# InkTime_Schematic.net
KiCad netlist of a schematic drawn in EAGLE
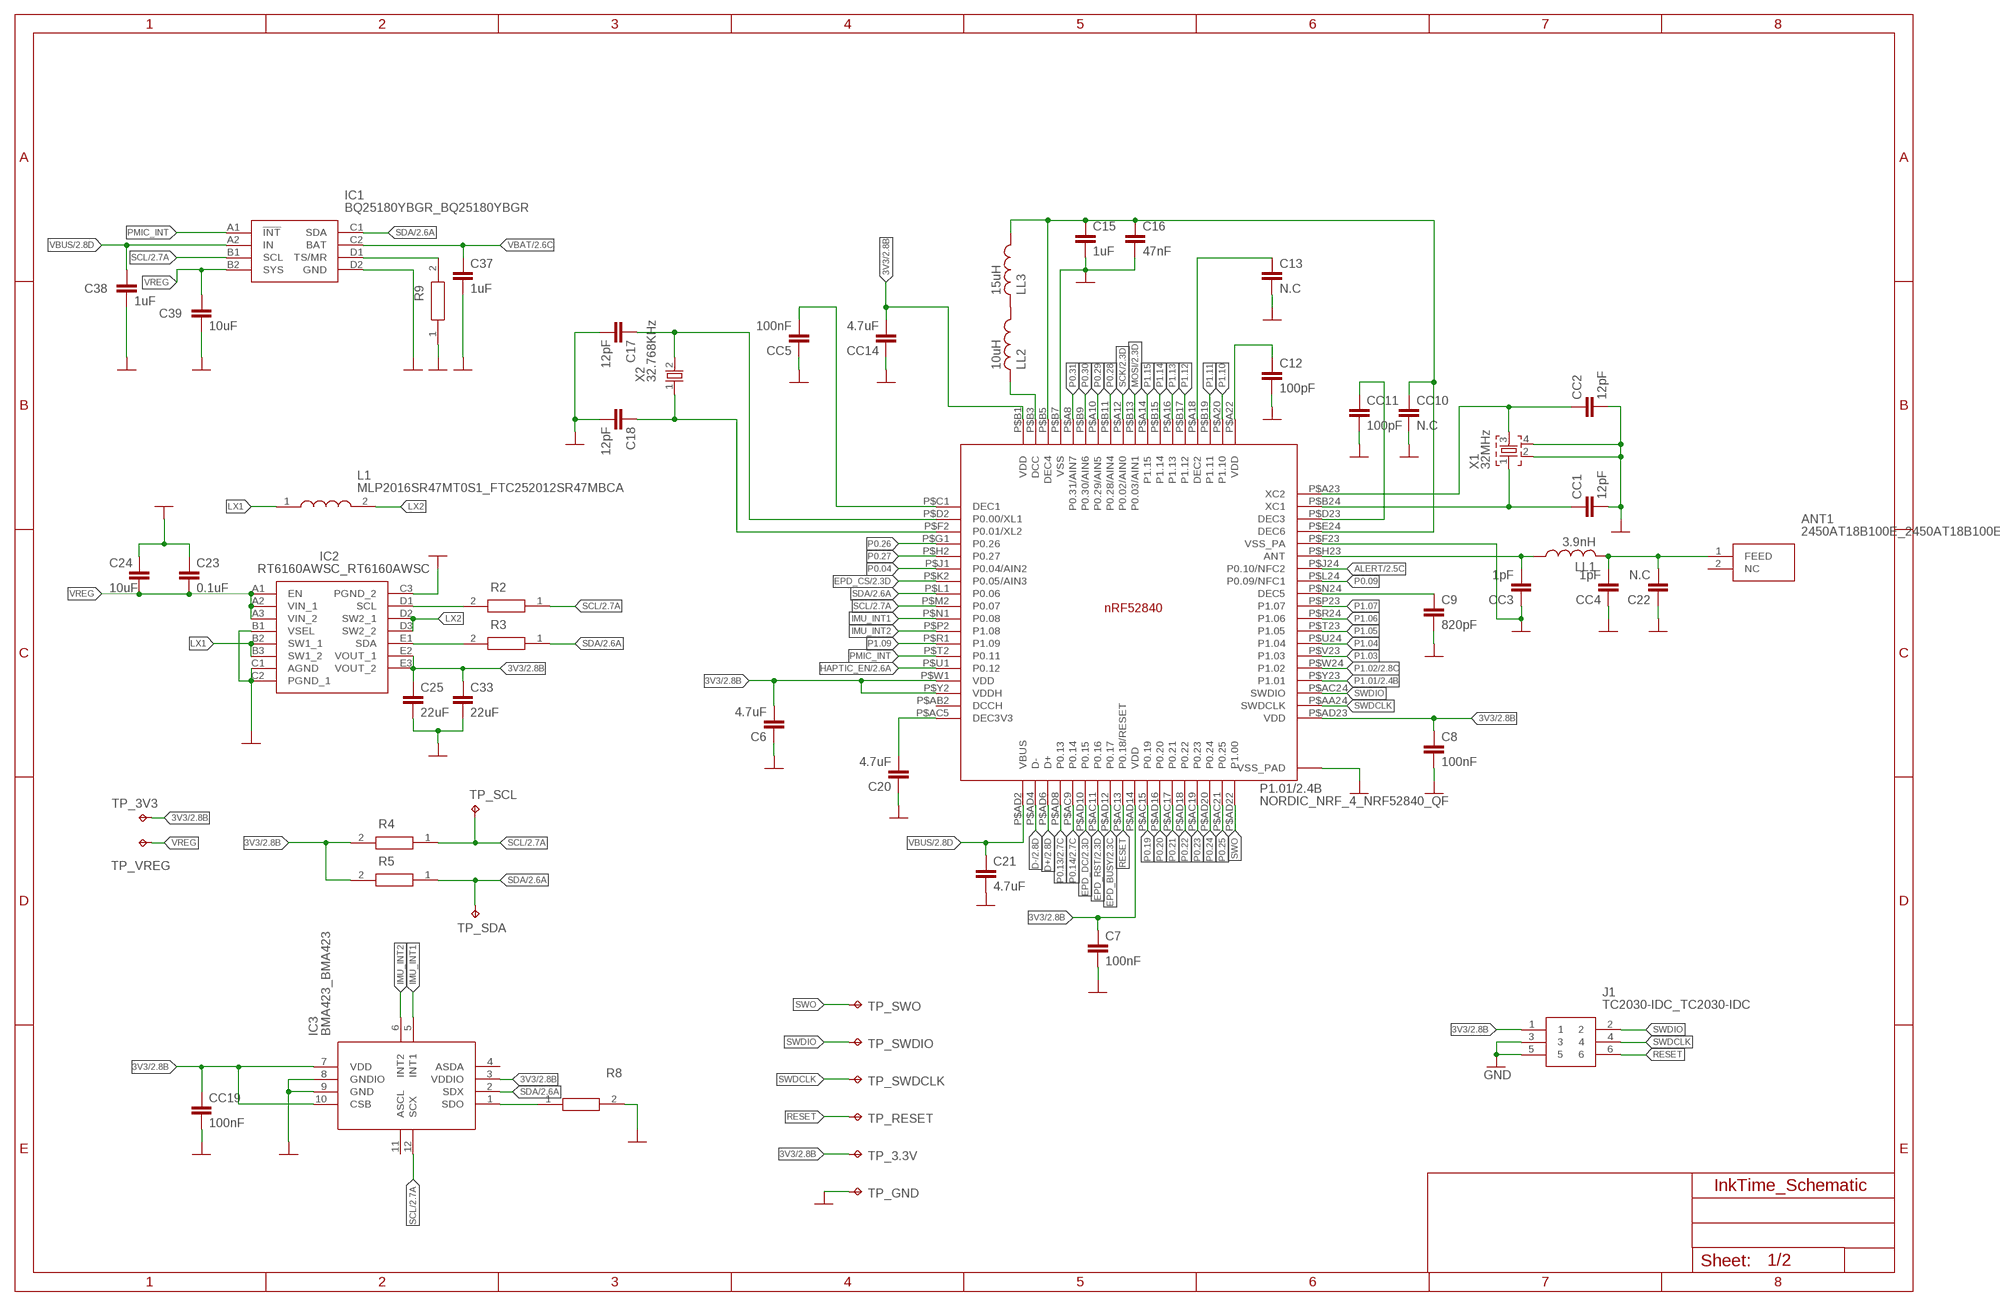
[diagram p0: schematic, sheet 1]
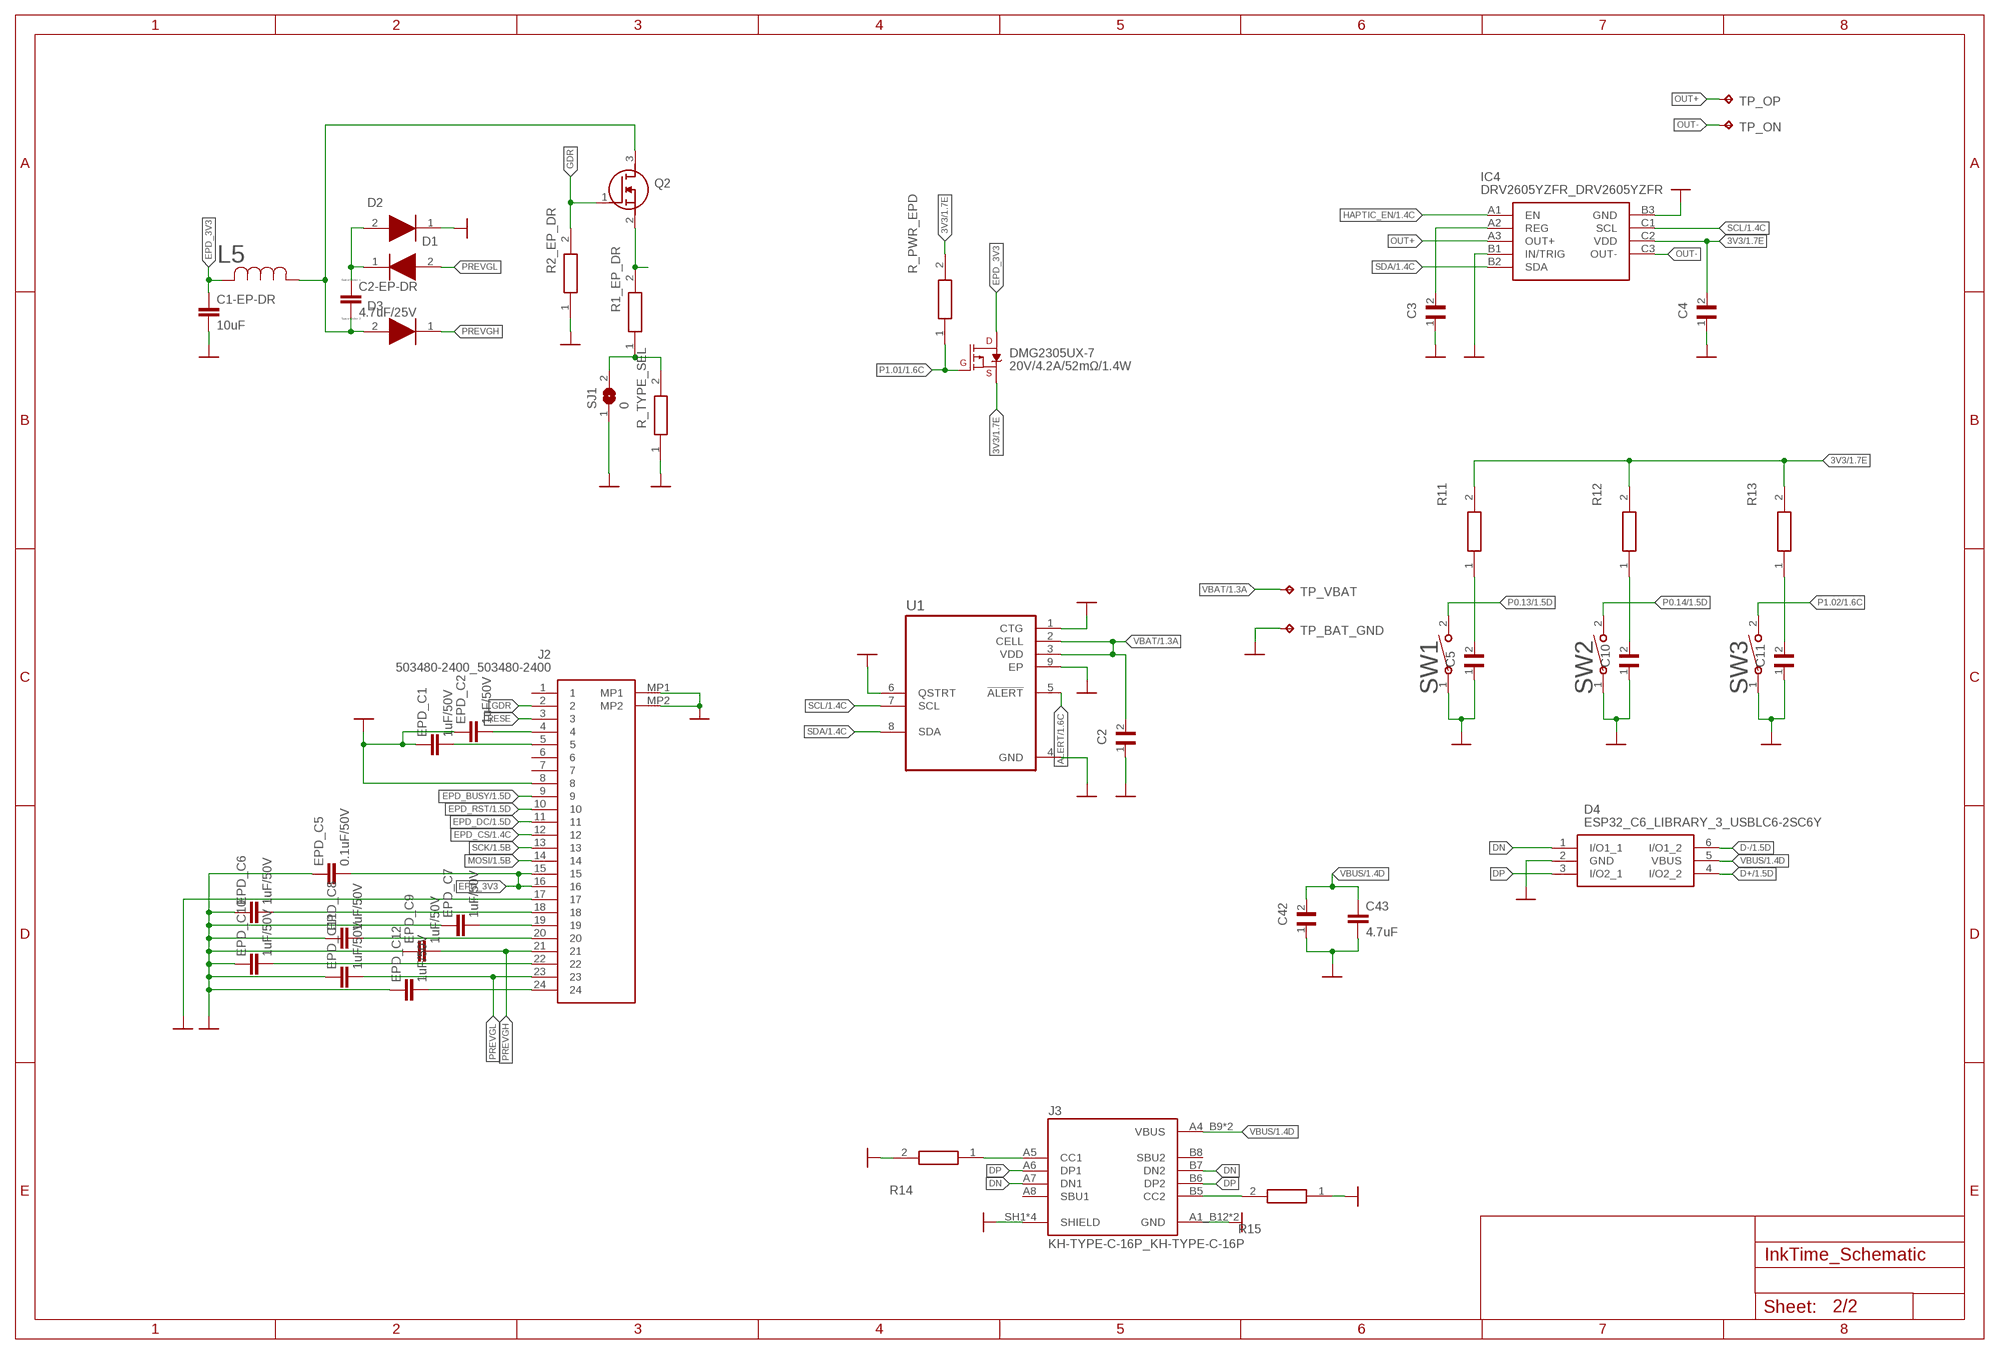
[diagram p1: schematic, sheet 2]

(export (version "E")
  (design (tool "Eeschema 10.0.6"))
  (components
    (comp (ref "C1-EP-DR")
      (value "10uF")
      (footprint "eagle-import:NORDIC_NRF_3_RESC0402_M")
      (libsource (lib "eagle-import") (part "NORDIC_NRF_3_CAPACITOR_0402_M"))
    )
    (comp (ref "C2")
      (value "GRM011R60J152KE01L_1_GRM011R60J152KE01L")
      (footprint "eagle-import:GRM011R60J152KE01L_1_0201")
      (libsource (lib "eagle-import") (part "GRM011R60J152KE01L_1_GRM011R60J152KE01L"))
    )
    (comp (ref "C2-EP-DR")
      (value "4.7uF/25V")
      (footprint "eagle-import:ESP32_C6_LIBRARY_1_ESP32_WROVER_EAGLE-LTSPICE_C0402")
      (libsource (lib "eagle-import") (part "ESP32_C6_LIBRARY_1_ESP32_WROVER_EAGLE-LTSPICE_CC0402"))
    )
    (comp (ref "C3")
      (value "1uF")
      (footprint "eagle-import:GRM011R60J152KE01L_1_0201")
      (libsource (lib "eagle-import") (part "GRM011R60J152KE01L_1_GRM011R60J152KE01L"))
    )
    (comp (ref "C4")
      (value "0.1uF")
      (footprint "eagle-import:GRM011R60J152KE01L_1_0201")
      (libsource (lib "eagle-import") (part "GRM011R60J152KE01L_1_GRM011R60J152KE01L"))
    )
    (comp (ref "C5")
      (value "GRM011R60J152KE01L_1_GRM011R60J152KE01L")
      (footprint "eagle-import:GRM011R60J152KE01L_1_0201")
      (libsource (lib "eagle-import") (part "GRM011R60J152KE01L_1_GRM011R60J152KE01L"))
    )
    (comp (ref "C10")
      (value "GRM011R60J152KE01L_1_GRM011R60J152KE01L")
      (footprint "eagle-import:GRM011R60J152KE01L_1_0201")
      (libsource (lib "eagle-import") (part "GRM011R60J152KE01L_1_GRM011R60J152KE01L"))
    )
    (comp (ref "C11")
      (value "GRM011R60J152KE01L_1_GRM011R60J152KE01L")
      (footprint "eagle-import:GRM011R60J152KE01L_1_0201")
      (libsource (lib "eagle-import") (part "GRM011R60J152KE01L_1_GRM011R60J152KE01L"))
    )
    (comp (ref "C42")
      (value "GRM011R60J152KE01L_1_GRM011R60J152KE01L")
      (footprint "eagle-import:GRM011R60J152KE01L_1_0201")
      (libsource (lib "eagle-import") (part "GRM011R60J152KE01L_1_GRM011R60J152KE01L"))
    )
    (comp (ref "C43")
      (value "4.7uF")
      (footprint "eagle-import:NORDIC_NRF_3_RESC0402_M")
      (libsource (lib "eagle-import") (part "NORDIC_NRF_3_CAPACITOR_0402_M"))
    )
    (comp (ref "D1")
      (value "ESP32_C6_LIBRARY_5_MBR0530")
      (footprint "eagle-import:ESP32_C6_LIBRARY_5_SOD3716X135N")
      (fields (field (name "MF") "ON Semiconductor") (field (name "MP") "MBR0530"))
      (libsource (lib "eagle-import") (part "ESP32_C6_LIBRARY_5_MBR0530"))
    )
    (comp (ref "D2")
      (value "ESP32_C6_LIBRARY_5_MBR0530")
      (footprint "eagle-import:ESP32_C6_LIBRARY_5_SOD3716X135N")
      (fields (field (name "MF") "ON Semiconductor") (field (name "MP") "MBR0530"))
      (libsource (lib "eagle-import") (part "ESP32_C6_LIBRARY_5_MBR0530"))
    )
    (comp (ref "D3")
      (value "ESP32_C6_LIBRARY_5_MBR0530")
      (footprint "eagle-import:ESP32_C6_LIBRARY_5_SOD3716X135N")
      (fields (field (name "MF") "ON Semiconductor") (field (name "MP") "MBR0530"))
      (libsource (lib "eagle-import") (part "ESP32_C6_LIBRARY_5_MBR0530"))
    )
    (comp (ref "D4")
      (value "ESP32_C6_LIBRARY_3_USBLC6-2SC6Y")
      (footprint "eagle-import:ESP32_C6_LIBRARY_3_SOT95P280X145-6N")
      (fields (field (name "MF") "STMicroelectronics") (field (name "MP") "USBLC6-2SC6Y"))
      (libsource (lib "eagle-import") (part "ESP32_C6_LIBRARY_3_USBLC6-2SC6Y"))
    )
    (comp (ref "DMG2305UX-7")
      (value "20V/4.2A/52mΩ/1.4W")
      (footprint "eagle-import:ESP32_C6_LIBRARY_4_ESP32_C6_LIBRARY_4_ESP32_C6_LIBRARY_4_ESP32_C6_LIBRARY_4_ESP32_WROVER_SPARKFUN-DISCRETESEMI_SOT23-3")
      (libsource (lib "eagle-import") (part "ESP32_C6_LIBRARY_4_ESP32_WROVER_SPARKFUN-DISCRETESEMI_MOSFET_PCH-DMG2305UX-7"))
    )
    (comp (ref "EPD_C1")
      (value "1uF/50V")
      (footprint "eagle-import:NORDIC_NRF_3_RESC0402_M")
      (libsource (lib "eagle-import") (part "NORDIC_NRF_3_CAPACITOR_0402_M"))
    )
    (comp (ref "EPD_C2")
      (value "1uF/50V")
      (footprint "eagle-import:NORDIC_NRF_3_RESC0402_M")
      (libsource (lib "eagle-import") (part "NORDIC_NRF_3_CAPACITOR_0402_M"))
    )
    (comp (ref "EPD_C5")
      (value "0.1uF/50V")
      (footprint "eagle-import:NORDIC_NRF_3_RESC0402_M")
      (libsource (lib "eagle-import") (part "NORDIC_NRF_3_CAPACITOR_0402_M"))
    )
    (comp (ref "EPD_C6")
      (value "1uF/50V")
      (footprint "eagle-import:NORDIC_NRF_3_RESC0402_M")
      (libsource (lib "eagle-import") (part "NORDIC_NRF_3_CAPACITOR_0402_M"))
    )
    (comp (ref "EPD_C7")
      (value "1uF/50V")
      (footprint "eagle-import:NORDIC_NRF_3_RESC0402_M")
      (libsource (lib "eagle-import") (part "NORDIC_NRF_3_CAPACITOR_0402_M"))
    )
    (comp (ref "EPD_C8")
      (value "1uF/50V")
      (footprint "eagle-import:NORDIC_NRF_3_RESC0402_M")
      (libsource (lib "eagle-import") (part "NORDIC_NRF_3_CAPACITOR_0402_M"))
    )
    (comp (ref "EPD_C9")
      (value "1uF/50V")
      (footprint "eagle-import:NORDIC_NRF_3_RESC0402_M")
      (libsource (lib "eagle-import") (part "NORDIC_NRF_3_CAPACITOR_0402_M"))
    )
    (comp (ref "EPD_C10")
      (value "1uF/50V")
      (footprint "eagle-import:NORDIC_NRF_3_RESC0402_M")
      (libsource (lib "eagle-import") (part "NORDIC_NRF_3_CAPACITOR_0402_M"))
    )
    (comp (ref "EPD_C11")
      (value "1uF/50V")
      (footprint "eagle-import:NORDIC_NRF_3_RESC0402_M")
      (libsource (lib "eagle-import") (part "NORDIC_NRF_3_CAPACITOR_0402_M"))
    )
    (comp (ref "EPD_C12")
      (value "1uF/50V")
      (footprint "eagle-import:NORDIC_NRF_3_RESC0402_M")
      (libsource (lib "eagle-import") (part "NORDIC_NRF_3_CAPACITOR_0402_M"))
    )
    (comp (ref "IC4")
      (value "DRV2605YZFR_DRV2605YZFR")
      (footprint "eagle-import:DRV2605YZFR_BGA9C50P3X3_144X144X62")
      (fields (field (name "ARROW_PART_NUMBER") "DRV2605YZFR"))
      (libsource (lib "eagle-import") (part "DRV2605YZFR_DRV2605YZFR"))
    )
    (comp (ref "J2")
      (value "503480-2400_503480-2400")
      (footprint "eagle-import:503480-2400_5034802400")
      (fields
        (field (name "MANUFACTURER_PART_NUMBER") "503480-2400")
        (field (name "MOUSER_PART_NUMBER") "538-503480-2400")
      )
      (libsource (lib "eagle-import") (part "503480-2400_503480-2400"))
    )
    (comp (ref "J3")
      (value "KH-TYPE-C-16P_KH-TYPE-C-16P")
      (footprint "eagle-import:KH-TYPE-C-16P_KINGHELM_KH-TYPE-C-16P")
      (fields (field (name "MF") "kinghelm") (field (name "MP") "KH-TYPE-C-16P"))
      (libsource (lib "eagle-import") (part "KH-TYPE-C-16P_KH-TYPE-C-16P"))
    )
    (comp (ref "L5")
      (value "ESP32_C6_LIBRARY_2_744043680IND_4828-WE-TPC_WRE")
      (footprint "eagle-import:ESP32_C6_LIBRARY_2_IND_4828-WE-TPC_WRE")
      (fields
        (field (name "MANUFACTURER_PART_NUMBER") "744043680")
        (field (name "COPYRIGHT") "Copyright (C) 2024 Ultra Librarian. All rights reserved.")
      )
      (libsource (lib "eagle-import") (part "ESP32_C6_LIBRARY_2_744043680IND_4828-WE-TPC_WRE"))
    )
    (comp (ref "Q2")
      (value "ESP32_C6_LIBRARY_6_SI1308EDL-T1-GE3")
      (footprint "eagle-import:ESP32_C6_LIBRARY_6_SOT65P210X110-3N")
      (fields (field (name "MF") "Vishay Siliconix") (field (name "MP") "SI1308EDL-T1-GE3"))
      (libsource (lib "eagle-import") (part "ESP32_C6_LIBRARY_6_SI1308EDL-T1-GE3"))
    )
    (comp (ref "R1_EP_DR")
      (value "CPF0201D7K68C1_CPF0201D7K68C1")
      (footprint "eagle-import:CPF0201D7K68C1_0201")
      (libsource (lib "eagle-import") (part "CPF0201D7K68C1_CPF0201D7K68C1"))
    )
    (comp (ref "R2_EP_DR")
      (value "CPF0201D7K68C1_CPF0201D7K68C1")
      (footprint "eagle-import:CPF0201D7K68C1_0201")
      (libsource (lib "eagle-import") (part "CPF0201D7K68C1_CPF0201D7K68C1"))
    )
    (comp (ref "R11")
      (value "CPF0201D7K68C1_CPF0201D7K68C1")
      (footprint "eagle-import:CPF0201D7K68C1_0201")
      (libsource (lib "eagle-import") (part "CPF0201D7K68C1_CPF0201D7K68C1"))
    )
    (comp (ref "R12")
      (value "CPF0201D7K68C1_CPF0201D7K68C1")
      (footprint "eagle-import:CPF0201D7K68C1_0201")
      (libsource (lib "eagle-import") (part "CPF0201D7K68C1_CPF0201D7K68C1"))
    )
    (comp (ref "R13")
      (value "CPF0201D7K68C1_CPF0201D7K68C1")
      (footprint "eagle-import:CPF0201D7K68C1_0201")
      (libsource (lib "eagle-import") (part "CPF0201D7K68C1_CPF0201D7K68C1"))
    )
    (comp (ref "R14")
      (value "CPF0201D7K68C1_CPF0201D7K68C1")
      (footprint "eagle-import:CPF0201D7K68C1_0201")
      (libsource (lib "eagle-import") (part "CPF0201D7K68C1_CPF0201D7K68C1"))
    )
    (comp (ref "R15")
      (value "CPF0201D7K68C1_CPF0201D7K68C1")
      (footprint "eagle-import:CPF0201D7K68C1_0201")
      (libsource (lib "eagle-import") (part "CPF0201D7K68C1_CPF0201D7K68C1"))
    )
    (comp (ref "R_PWR_EPD")
      (value "CPF0201D7K68C1_CPF0201D7K68C1")
      (footprint "eagle-import:CPF0201D7K68C1_0201")
      (libsource (lib "eagle-import") (part "CPF0201D7K68C1_CPF0201D7K68C1"))
    )
    (comp (ref "R_TYPE_SEL")
      (value "CPF0201D7K68C1_CPF0201D7K68C1")
      (footprint "eagle-import:CPF0201D7K68C1_0201")
      (libsource (lib "eagle-import") (part "CPF0201D7K68C1_CPF0201D7K68C1"))
    )
    (comp (ref "SJ1")
      (value "0")
      (footprint "eagle-import:ESP32_C6_LIBRARY_7_JUMPER_SJ")
      (libsource (lib "eagle-import") (part "ESP32_C6_LIBRARY_7_JUMPER_SJ"))
    )
    (comp (ref "SW1")
      (value "2025-10-22_07-23-44_LIBRARY_EVP-AKE31ASW_EVP-AKE31A_PAN")
      (footprint "eagle-import:2025-10-22_07-23-44_LIBRARY_SW_EVP-AKE31A_PAN")
      (fields
        (field (name "MANUFACTURER_PART_NUMBER") "EVP-AKE31A")
        (field (name "COPYRIGHT") "Copyright (C) 2025 Ultra Librarian. All rights reserved.")
      )
      (libsource (lib "eagle-import") (part "2025-10-22_07-23-44_LIBRARY_EVP-AKE31ASW_EVP-AKE31A_PAN"))
    )
    (comp (ref "SW2")
      (value "2025-10-22_07-23-44_LIBRARY_EVP-AKE31ASW_EVP-AKE31A_PAN")
      (footprint "eagle-import:2025-10-22_07-23-44_LIBRARY_SW_EVP-AKE31A_PAN")
      (fields
        (field (name "MANUFACTURER_PART_NUMBER") "EVP-AKE31A")
        (field (name "COPYRIGHT") "Copyright (C) 2025 Ultra Librarian. All rights reserved.")
      )
      (libsource (lib "eagle-import") (part "2025-10-22_07-23-44_LIBRARY_EVP-AKE31ASW_EVP-AKE31A_PAN"))
    )
    (comp (ref "SW3")
      (value "2025-10-22_07-23-44_LIBRARY_EVP-AKE31ASW_EVP-AKE31A_PAN")
      (footprint "eagle-import:2025-10-22_07-23-44_LIBRARY_SW_EVP-AKE31A_PAN")
      (fields
        (field (name "MANUFACTURER_PART_NUMBER") "EVP-AKE31A")
        (field (name "COPYRIGHT") "Copyright (C) 2025 Ultra Librarian. All rights reserved.")
      )
      (libsource (lib "eagle-import") (part "2025-10-22_07-23-44_LIBRARY_EVP-AKE31ASW_EVP-AKE31A_PAN"))
    )
    (comp (ref "TP_BAT_GND")
      (value "HECTOR_WATCH_1_TPTP20R")
      (footprint "eagle-import:HECTOR_WATCH_1_TP20R")
      (libsource (lib "eagle-import") (part "HECTOR_WATCH_1_TPTP20R"))
    )
    (comp (ref "TP_ON")
      (value "HECTOR_WATCH_1_TPTP20R")
      (footprint "eagle-import:HECTOR_WATCH_1_TP20R")
      (libsource (lib "eagle-import") (part "HECTOR_WATCH_1_TPTP20R"))
    )
    (comp (ref "TP_OP")
      (value "HECTOR_WATCH_1_TPTP20R")
      (footprint "eagle-import:HECTOR_WATCH_1_TP20R")
      (libsource (lib "eagle-import") (part "HECTOR_WATCH_1_TPTP20R"))
    )
    (comp (ref "TP_VBAT")
      (value "HECTOR_WATCH_1_TPTP20R")
      (footprint "eagle-import:HECTOR_WATCH_1_TP20R")
      (libsource (lib "eagle-import") (part "HECTOR_WATCH_1_TPTP20R"))
    )
    (comp (ref "U1")
      (value "ESP32_C6_LIBRARY_MAX17048G+T10")
      (footprint "eagle-import:ESP32_C6_LIBRARY_SON50P200X200X80-9N")
      (fields (field (name "MF") "Analog Devices") (field (name "MP") "MAX17048G+T10"))
      (libsource (lib "eagle-import") (part "ESP32_C6_LIBRARY_MAX17048G+T10"))
    )
    (comp (ref "ANT1")
      (value "2450AT18B100E_2450AT18B100E")
      (footprint "eagle-import:2450AT18B100E_ANTC3216X140N")
      (fields
        (field (name "ARROW_PART_NUMBER") "2450AT18B100E")
        (field (name "MOUSER_PART_NUMBER") "609-2450AT18B100E")
      )
      (libsource (lib "eagle-import") (part "2450AT18B100E_2450AT18B100E"))
    )
    (comp (ref "C6")
      (value "4.7uF")
      (footprint "eagle-import:NORDIC_NRF_3_RESC0402_M")
      (libsource (lib "eagle-import") (part "NORDIC_NRF_3_CAPACITOR_0402_M"))
    )
    (comp (ref "C7")
      (value "100nF")
      (footprint "eagle-import:NORDIC_NRF_3_RESC0402_M")
      (libsource (lib "eagle-import") (part "NORDIC_NRF_3_CAPACITOR_0402_M"))
    )
    (comp (ref "C8")
      (value "100nF")
      (footprint "eagle-import:NORDIC_NRF_3_RESC0402_M")
      (libsource (lib "eagle-import") (part "NORDIC_NRF_3_CAPACITOR_0402_M"))
    )
    (comp (ref "C9")
      (value "820pF")
      (footprint "eagle-import:NORDIC_NRF_3_RESC0402_M")
      (libsource (lib "eagle-import") (part "NORDIC_NRF_3_CAPACITOR_0402_M"))
    )
    (comp (ref "C12")
      (value "100pF")
      (footprint "eagle-import:NORDIC_NRF_3_RESC0402_M")
      (libsource (lib "eagle-import") (part "NORDIC_NRF_3_CAPACITOR_0402_M"))
    )
    (comp (ref "C13")
      (value "N.C")
      (footprint "eagle-import:NORDIC_NRF_3_RESC0402_M")
      (libsource (lib "eagle-import") (part "NORDIC_NRF_3_CAPACITOR_0402_M"))
    )
    (comp (ref "C15")
      (value "1uF")
      (footprint "eagle-import:NORDIC_NRF_3_RESC0402_M")
      (libsource (lib "eagle-import") (part "NORDIC_NRF_3_CAPACITOR_0402_M"))
    )
    (comp (ref "C16")
      (value "47nF")
      (footprint "eagle-import:NORDIC_NRF_3_RESC0402_M")
      (libsource (lib "eagle-import") (part "NORDIC_NRF_3_CAPACITOR_0402_M"))
    )
    (comp (ref "C17")
      (value "12pF")
      (footprint "eagle-import:NORDIC_NRF_3_RESC0402_M")
      (libsource (lib "eagle-import") (part "NORDIC_NRF_3_CAPACITOR_0402_M"))
    )
    (comp (ref "C18")
      (value "12pF")
      (footprint "eagle-import:NORDIC_NRF_3_RESC0402_M")
      (libsource (lib "eagle-import") (part "NORDIC_NRF_3_CAPACITOR_0402_M"))
    )
    (comp (ref "C20")
      (value "4.7uF")
      (footprint "eagle-import:NORDIC_NRF_3_RESC0402_M")
      (libsource (lib "eagle-import") (part "NORDIC_NRF_3_CAPACITOR_0402_M"))
    )
    (comp (ref "C21")
      (value "4.7uF")
      (footprint "eagle-import:NORDIC_NRF_3_RESC0402_M")
      (libsource (lib "eagle-import") (part "NORDIC_NRF_3_CAPACITOR_0402_M"))
    )
    (comp (ref "C22")
      (value "N.C")
      (footprint "eagle-import:NORDIC_NRF_3_RESC0402_M")
      (libsource (lib "eagle-import") (part "NORDIC_NRF_3_CAPACITOR_0402_M"))
    )
    (comp (ref "C23")
      (value "0.1uF")
      (footprint "eagle-import:NORDIC_NRF_3_RESC0402_M")
      (libsource (lib "eagle-import") (part "NORDIC_NRF_3_CAPACITOR_0402_M"))
    )
    (comp (ref "C24")
      (value "10uF")
      (footprint "eagle-import:NORDIC_NRF_3_RESC0402_M")
      (libsource (lib "eagle-import") (part "NORDIC_NRF_3_CAPACITOR_0402_M"))
    )
    (comp (ref "C25")
      (value "22uF")
      (footprint "eagle-import:NORDIC_NRF_3_RESC0402_M")
      (libsource (lib "eagle-import") (part "NORDIC_NRF_3_CAPACITOR_0402_M"))
    )
    (comp (ref "C33")
      (value "22uF")
      (footprint "eagle-import:NORDIC_NRF_3_RESC0402_M")
      (libsource (lib "eagle-import") (part "NORDIC_NRF_3_CAPACITOR_0402_M"))
    )
    (comp (ref "C37")
      (value "1uF")
      (footprint "eagle-import:NORDIC_NRF_3_RESC0402_M")
      (libsource (lib "eagle-import") (part "NORDIC_NRF_3_CAPACITOR_0402_M"))
    )
    (comp (ref "C38")
      (value "1uF")
      (footprint "eagle-import:NORDIC_NRF_3_RESC0402_M")
      (libsource (lib "eagle-import") (part "NORDIC_NRF_3_CAPACITOR_0402_M"))
    )
    (comp (ref "C39")
      (value "10uF")
      (footprint "eagle-import:NORDIC_NRF_3_RESC0402_M")
      (libsource (lib "eagle-import") (part "NORDIC_NRF_3_CAPACITOR_0402_M"))
    )
    (comp (ref "CC1")
      (value "12pF")
      (footprint "eagle-import:NORDIC_NRF_3_RESC0402_M")
      (libsource (lib "eagle-import") (part "NORDIC_NRF_3_CAPACITOR_0402_M"))
    )
    (comp (ref "CC2")
      (value "12pF")
      (footprint "eagle-import:NORDIC_NRF_3_RESC0402_M")
      (libsource (lib "eagle-import") (part "NORDIC_NRF_3_CAPACITOR_0402_M"))
    )
    (comp (ref "CC3")
      (value "1pF")
      (footprint "eagle-import:NORDIC_NRF_3_RESC0402_M")
      (libsource (lib "eagle-import") (part "NORDIC_NRF_3_CAPACITOR_0402_M"))
    )
    (comp (ref "CC4")
      (value "1pF")
      (footprint "eagle-import:NORDIC_NRF_3_RESC0402_M")
      (libsource (lib "eagle-import") (part "NORDIC_NRF_3_CAPACITOR_0402_M"))
    )
    (comp (ref "CC5")
      (value "100nF")
      (footprint "eagle-import:NORDIC_NRF_3_RESC0402_M")
      (libsource (lib "eagle-import") (part "NORDIC_NRF_3_CAPACITOR_0402_M"))
    )
    (comp (ref "CC10")
      (value "N.C")
      (footprint "eagle-import:NORDIC_NRF_3_RESC0402_M")
      (libsource (lib "eagle-import") (part "NORDIC_NRF_3_CAPACITOR_0402_M"))
    )
    (comp (ref "CC11")
      (value "100pF")
      (footprint "eagle-import:NORDIC_NRF_3_RESC0402_M")
      (libsource (lib "eagle-import") (part "NORDIC_NRF_3_CAPACITOR_0402_M"))
    )
    (comp (ref "CC14")
      (value "4.7uF")
      (footprint "eagle-import:NORDIC_NRF_3_RESC0402_M")
      (libsource (lib "eagle-import") (part "NORDIC_NRF_3_CAPACITOR_0402_M"))
    )
    (comp (ref "CC19")
      (value "100nF")
      (footprint "eagle-import:NORDIC_NRF_3_RESC0402_M")
      (libsource (lib "eagle-import") (part "NORDIC_NRF_3_CAPACITOR_0402_M"))
    )
    (comp (ref "IC1")
      (value "BQ25180YBGR_BQ25180YBGR")
      (footprint "eagle-import:BQ25180YBGR_BGA8C40P2X4_100X155X50")
      (fields
        (field (name "ARROW_PART_NUMBER") "BQ25180YBGR")
        (field (name "MOUSER_PART_NUMBER") "595-BQ25180YBGR")
      )
      (libsource (lib "eagle-import") (part "BQ25180YBGR_BQ25180YBGR"))
    )
    (comp (ref "IC2")
      (value "RT6160AWSC_RT6160AWSC")
      (footprint "eagle-import:RT6160AWSC_BGA15C40P3X5_140X230X60")
      (fields
        (field (name "MANUFACTURER_PART_NUMBER") "RT6160AWSC")
        (field (name "MOUSER_PART_NUMBER") "835-RT6160AWSC")
      )
      (libsource (lib "eagle-import") (part "RT6160AWSC_RT6160AWSC"))
    )
    (comp (ref "IC3")
      (value "BMA423_BMA423")
      (footprint "eagle-import:BMA423_BMA423")
      (fields (field (name "ARROW_PART_NUMBER") "BMA423") (field (name "MOUSER_PART_NUMBER") "262-BMA423"))
      (libsource (lib "eagle-import") (part "BMA423_BMA423"))
    )
    (comp (ref "J1")
      (value "TC2030-IDC_TC2030-IDC")
      (footprint "eagle-import:TC2030-IDC_TC2030IDC")
      (fields (field (name "MANUFACTURER_PART_NUMBER") "TC2030-IDC"))
      (libsource (lib "eagle-import") (part "TC2030-IDC_TC2030-IDC"))
    )
    (comp (ref "L1")
      (value "MLP2016SR47MT0S1_FTC252012SR47MBCA")
      (footprint "eagle-import:MLP2016SR47MT0S1_INDC2016X100N")
      (fields (field (name "MANUFACTURER_PART_NUMBER") "FTC252012SR47MBCA"))
      (libsource (lib "eagle-import") (part "MLP2016SR47MT0S1_FTC252012SR47MBCA"))
    )
    (comp (ref "LL1")
      (value "3.9nH")
      (footprint "eagle-import:NORDIC_NRF_2_RESC0402_M")
      (libsource (lib "eagle-import") (part "NORDIC_NRF_2_INDUCTOR_0402_M"))
    )
    (comp (ref "LL2")
      (value "10uH")
      (footprint "eagle-import:NORDIC_NRF_2_RESC0402_M")
      (libsource (lib "eagle-import") (part "NORDIC_NRF_2_INDUCTOR_0402_M"))
    )
    (comp (ref "LL3")
      (value "15uH")
      (footprint "eagle-import:NORDIC_NRF_2_RESC0402_M")
      (libsource (lib "eagle-import") (part "NORDIC_NRF_2_INDUCTOR_0402_M"))
    )
    (comp (ref "P1.01/2.4B")
      (value "NORDIC_NRF_4_NRF52840_QF")
      (footprint "eagle-import:NORDIC_NRF_4_AQFN50P700X700X85_HS-74N")
      (libsource (lib "eagle-import") (part "NORDIC_NRF_4_NRF52840_QF"))
    )
    (comp (ref "R2")
      (value "CPF0201D7K68C1_CPF0201D7K68C1")
      (footprint "eagle-import:CPF0201D7K68C1_0201")
      (libsource (lib "eagle-import") (part "CPF0201D7K68C1_CPF0201D7K68C1"))
    )
    (comp (ref "R3")
      (value "CPF0201D7K68C1_CPF0201D7K68C1")
      (footprint "eagle-import:CPF0201D7K68C1_0201")
      (libsource (lib "eagle-import") (part "CPF0201D7K68C1_CPF0201D7K68C1"))
    )
    (comp (ref "R4")
      (value "CPF0201D7K68C1_CPF0201D7K68C1")
      (footprint "eagle-import:CPF0201D7K68C1_0201")
      (libsource (lib "eagle-import") (part "CPF0201D7K68C1_CPF0201D7K68C1"))
    )
    (comp (ref "R5")
      (value "CPF0201D7K68C1_CPF0201D7K68C1")
      (footprint "eagle-import:CPF0201D7K68C1_0201")
      (libsource (lib "eagle-import") (part "CPF0201D7K68C1_CPF0201D7K68C1"))
    )
    (comp (ref "R8")
      (value "CPF0201D7K68C1_CPF0201D7K68C1")
      (footprint "eagle-import:CPF0201D7K68C1_0201")
      (libsource (lib "eagle-import") (part "CPF0201D7K68C1_CPF0201D7K68C1"))
    )
    (comp (ref "R9")
      (value "10K")
      (footprint "eagle-import:CPF0201D7K68C1_0201")
      (libsource (lib "eagle-import") (part "CPF0201D7K68C1_CPF0201D7K68C1"))
    )
    (comp (ref "TP_3.3V")
      (value "HECTOR_WATCH_1_TPTP20R")
      (footprint "eagle-import:HECTOR_WATCH_1_TP20R")
      (libsource (lib "eagle-import") (part "HECTOR_WATCH_1_TPTP20R"))
    )
    (comp (ref "TP_3V3")
      (value "HECTOR_WATCH_1_TPTP20R")
      (footprint "eagle-import:HECTOR_WATCH_1_TP20R")
      (libsource (lib "eagle-import") (part "HECTOR_WATCH_1_TPTP20R"))
    )
    (comp (ref "TP_GND")
      (value "HECTOR_WATCH_1_TPTP20R")
      (footprint "eagle-import:HECTOR_WATCH_1_TP20R")
      (libsource (lib "eagle-import") (part "HECTOR_WATCH_1_TPTP20R"))
    )
    (comp (ref "TP_RESET")
      (value "HECTOR_WATCH_1_TPTP20R")
      (footprint "eagle-import:HECTOR_WATCH_1_TP20R")
      (libsource (lib "eagle-import") (part "HECTOR_WATCH_1_TPTP20R"))
    )
    (comp (ref "TP_SCL")
      (value "HECTOR_WATCH_1_TPTP20R")
      (footprint "eagle-import:HECTOR_WATCH_1_TP20R")
      (libsource (lib "eagle-import") (part "HECTOR_WATCH_1_TPTP20R"))
    )
    (comp (ref "TP_SDA")
      (value "HECTOR_WATCH_1_TPTP20R")
      (footprint "eagle-import:HECTOR_WATCH_1_TP20R")
      (libsource (lib "eagle-import") (part "HECTOR_WATCH_1_TPTP20R"))
    )
    (comp (ref "TP_SWDCLK")
      (value "HECTOR_WATCH_1_TPTP20R")
      (footprint "eagle-import:HECTOR_WATCH_1_TP20R")
      (libsource (lib "eagle-import") (part "HECTOR_WATCH_1_TPTP20R"))
    )
    (comp (ref "TP_SWDIO")
      (value "HECTOR_WATCH_1_TPTP20R")
      (footprint "eagle-import:HECTOR_WATCH_1_TP20R")
      (libsource (lib "eagle-import") (part "HECTOR_WATCH_1_TPTP20R"))
    )
    (comp (ref "TP_SWO")
      (value "HECTOR_WATCH_1_TPTP20R")
      (footprint "eagle-import:HECTOR_WATCH_1_TP20R")
      (libsource (lib "eagle-import") (part "HECTOR_WATCH_1_TPTP20R"))
    )
    (comp (ref "TP_VREG")
      (value "HECTOR_WATCH_1_TPTP20R")
      (footprint "eagle-import:HECTOR_WATCH_1_TP20R")
      (libsource (lib "eagle-import") (part "HECTOR_WATCH_1_TPTP20R"))
    )
    (comp (ref "X1")
      (value "32MHz")
      (footprint "eagle-import:NORDIC_NRF_BT-XTAL_2016_N")
      (libsource (lib "eagle-import") (part "NORDIC_NRF_XTAL_32MHZ"))
    )
    (comp (ref "X2")
      (value "32.768KHz")
      (footprint "eagle-import:NORDIC_NRF_1_XTAL_3215_N")
      (libsource (lib "eagle-import") (part "NORDIC_NRF_1_XTAL_32KHZ"))
    )
  )
  (nets
    (net (code "1") (name "3V3") (class "Default")
      (node (ref "C25") (pin "1") (pinfunction "1_1") (pintype "passive"))
      (node (ref "C33") (pin "1") (pinfunction "1_1") (pintype "passive"))
      (node (ref "C4") (pin "2") (pinfunction "2_2") (pintype "passive"))
      (node (ref "C6") (pin "2") (pinfunction "2_2") (pintype "passive"))
      (node (ref "C7") (pin "1") (pinfunction "1_1") (pintype "passive"))
      (node (ref "C8") (pin "1") (pinfunction "1_1") (pintype "passive"))
      (node (ref "CC14") (pin "2") (pinfunction "2_2") (pintype "passive"))
      (node (ref "CC19") (pin "1") (pinfunction "1_1") (pintype "passive"))
      (node (ref "DMG2305UX-7") (pin "2") (pinfunction "S_2") (pintype "bidirectional"))
      (node (ref "IC2") (pin "E2") (pinfunction "VOUT_1_E2") (pintype "bidirectional"))
      (node (ref "IC2") (pin "E3") (pinfunction "VOUT_2_E3") (pintype "bidirectional"))
      (node (ref "IC3") (pin "10") (pinfunction "CSB_10") (pintype "bidirectional"))
      (node (ref "IC3") (pin "3") (pinfunction "VDDIO_3") (pintype "bidirectional"))
      (node (ref "IC3") (pin "7") (pinfunction "VDD_7") (pintype "bidirectional"))
      (node (ref "IC4") (pin "C2") (pinfunction "VDD_C2") (pintype "bidirectional"))
      (node (ref "J1") (pin "1") (pinfunction "1_1") (pintype "bidirectional"))
      (node (ref "P1.01/2.4B") (pin "P$AD14") (pinfunction "VDD_P$AD14") (pintype "power_in"))
      (node (ref "P1.01/2.4B") (pin "P$AD23") (pinfunction "VDD_P$AD23") (pintype "power_in"))
      (node (ref "P1.01/2.4B") (pin "P$B1") (pinfunction "VDD_P$B1") (pintype "power_in"))
      (node (ref "P1.01/2.4B") (pin "P$W1") (pinfunction "VDD_P$W1") (pintype "power_in"))
      (node (ref "P1.01/2.4B") (pin "P$Y2") (pinfunction "VDDH_P$Y2") (pintype "power_in"))
      (node (ref "R11") (pin "2") (pinfunction "2_2") (pintype "bidirectional"))
      (node (ref "R12") (pin "2") (pinfunction "2_2") (pintype "bidirectional"))
      (node (ref "R13") (pin "2") (pinfunction "2_2") (pintype "bidirectional"))
      (node (ref "R4") (pin "2") (pinfunction "2_2") (pintype "bidirectional"))
      (node (ref "R5") (pin "2") (pinfunction "2_2") (pintype "bidirectional"))
      (node (ref "R_PWR_EPD") (pin "2") (pinfunction "2_2") (pintype "bidirectional"))
      (node (ref "TP_3.3V") (pin "TP") (pinfunction "TP_TP") (pintype "input"))
      (node (ref "TP_3V3") (pin "TP") (pinfunction "TP_TP") (pintype "input"))
    )
    (net (code "2") (name "ALERT") (class "Default")
      (node (ref "P1.01/2.4B") (pin "P$J24") (pinfunction "P0.10/NFC2_P$J24") (pintype "bidirectional"))
      (node (ref "U1") (pin "5") (pinfunction "~{ALERT}_5") (pintype "output"))
    )
    (net (code "3") (name "D+") (class "Default")
      (node (ref "D4") (pin "4") (pinfunction "I/O2_2_4") (pintype "bidirectional"))
      (node (ref "P1.01/2.4B") (pin "P$AD6") (pinfunction "D+_P$AD6") (pintype "bidirectional"))
    )
    (net (code "4") (name "D-") (class "Default")
      (node (ref "D4") (pin "6") (pinfunction "I/O1_2_6") (pintype "bidirectional"))
      (node (ref "P1.01/2.4B") (pin "P$AD4") (pinfunction "D-_P$AD4") (pintype "bidirectional"))
    )
    (net (code "5") (name "DN") (class "Default")
      (node (ref "D4") (pin "1") (pinfunction "I/O1_1_1") (pintype "bidirectional"))
      (node (ref "J3") (pin "A7") (pinfunction "DN1_A7") (pintype "bidirectional"))
      (node (ref "J3") (pin "B7") (pinfunction "DN2_B7") (pintype "bidirectional"))
    )
    (net (code "6") (name "DP") (class "Default")
      (node (ref "D4") (pin "3") (pinfunction "I/O2_1_3") (pintype "bidirectional"))
      (node (ref "J3") (pin "A6") (pinfunction "DP1_A6") (pintype "bidirectional"))
      (node (ref "J3") (pin "B6") (pinfunction "DP2_B6") (pintype "bidirectional"))
    )
    (net (code "7") (name "EPD_3V3") (class "Default")
      (node (ref "C1-EP-DR") (pin "1") (pinfunction "1_1") (pintype "passive"))
      (node (ref "DMG2305UX-7") (pin "3") (pinfunction "D_3") (pintype "bidirectional"))
      (node (ref "EPD_C5") (pin "2") (pinfunction "2_2") (pintype "passive"))
      (node (ref "J2") (pin "15") (pinfunction "15_15") (pintype "bidirectional"))
      (node (ref "J2") (pin "16") (pinfunction "16_16") (pintype "bidirectional"))
      (node (ref "L5") (pin "2") (pinfunction "2_2") (pintype "passive"))
    )
    (net (code "8") (name "EPD_BUSY") (class "Default")
      (node (ref "J2") (pin "9") (pinfunction "9_9") (pintype "bidirectional"))
      (node (ref "P1.01/2.4B") (pin "P$AD12") (pinfunction "P0.17_P$AD12") (pintype "bidirectional"))
    )
    (net (code "9") (name "EPD_CS") (class "Default")
      (node (ref "J2") (pin "12") (pinfunction "12_12") (pintype "bidirectional"))
      (node (ref "P1.01/2.4B") (pin "P$K2") (pinfunction "P0.05/AIN3_P$K2") (pintype "bidirectional"))
    )
    (net (code "10") (name "EPD_DC") (class "Default")
      (node (ref "J2") (pin "11") (pinfunction "11_11") (pintype "bidirectional"))
      (node (ref "P1.01/2.4B") (pin "P$AD10") (pinfunction "P0.15_P$AD10") (pintype "bidirectional"))
    )
    (net (code "11") (name "EPD_RST") (class "Default")
      (node (ref "J2") (pin "10") (pinfunction "10_10") (pintype "bidirectional"))
      (node (ref "P1.01/2.4B") (pin "P$AC11") (pinfunction "P0.16_P$AC11") (pintype "bidirectional"))
    )
    (net (code "12") (name "GDR") (class "Default")
      (node (ref "J2") (pin "2") (pinfunction "2_2") (pintype "bidirectional"))
      (node (ref "Q2") (pin "1") (pinfunction "G_1") (pintype "bidirectional"))
      (node (ref "R2_EP_DR") (pin "2") (pinfunction "2_2") (pintype "bidirectional"))
    )
    (net (code "13") (name "GND") (class "Default")
      (node (ref "C1-EP-DR") (pin "2") (pinfunction "2_2") (pintype "passive"))
      (node (ref "C10") (pin "1") (pinfunction "1_1") (pintype "passive"))
      (node (ref "C11") (pin "1") (pinfunction "1_1") (pintype "passive"))
      (node (ref "C12") (pin "2") (pinfunction "2_2") (pintype "passive"))
      (node (ref "C13") (pin "2") (pinfunction "2_2") (pintype "passive"))
      (node (ref "C15") (pin "2") (pinfunction "2_2") (pintype "passive"))
      (node (ref "C16") (pin "2") (pinfunction "2_2") (pintype "passive"))
      (node (ref "C17") (pin "2") (pinfunction "2_2") (pintype "passive"))
      (node (ref "C18") (pin "2") (pinfunction "2_2") (pintype "passive"))
      (node (ref "C2") (pin "1") (pinfunction "1_1") (pintype "passive"))
      (node (ref "C20") (pin "1") (pinfunction "1_1") (pintype "passive"))
      (node (ref "C21") (pin "2") (pinfunction "2_2") (pintype "passive"))
      (node (ref "C22") (pin "1") (pinfunction "1_1") (pintype "passive"))
      (node (ref "C23") (pin "1") (pinfunction "1_1") (pintype "passive"))
      (node (ref "C24") (pin "1") (pinfunction "1_1") (pintype "passive"))
      (node (ref "C25") (pin "2") (pinfunction "2_2") (pintype "passive"))
      (node (ref "C3") (pin "1") (pinfunction "1_1") (pintype "passive"))
      (node (ref "C33") (pin "2") (pinfunction "2_2") (pintype "passive"))
      (node (ref "C37") (pin "2") (pinfunction "2_2") (pintype "passive"))
      (node (ref "C38") (pin "2") (pinfunction "2_2") (pintype "passive"))
      (node (ref "C39") (pin "2") (pinfunction "2_2") (pintype "passive"))
      (node (ref "C4") (pin "1") (pinfunction "1_1") (pintype "passive"))
      (node (ref "C42") (pin "1") (pinfunction "1_1") (pintype "passive"))
      (node (ref "C43") (pin "2") (pinfunction "2_2") (pintype "passive"))
      (node (ref "C5") (pin "1") (pinfunction "1_1") (pintype "passive"))
      (node (ref "C6") (pin "1") (pinfunction "1_1") (pintype "passive"))
      (node (ref "C7") (pin "2") (pinfunction "2_2") (pintype "passive"))
      (node (ref "C8") (pin "2") (pinfunction "2_2") (pintype "passive"))
      (node (ref "C9") (pin "2") (pinfunction "2_2") (pintype "passive"))
      (node (ref "CC1") (pin "2") (pinfunction "2_2") (pintype "passive"))
      (node (ref "CC10") (pin "2") (pinfunction "2_2") (pintype "passive"))
      (node (ref "CC11") (pin "2") (pinfunction "2_2") (pintype "passive"))
      (node (ref "CC14") (pin "1") (pinfunction "1_1") (pintype "passive"))
      (node (ref "CC19") (pin "2") (pinfunction "2_2") (pintype "passive"))
      (node (ref "CC2") (pin "2") (pinfunction "2_2") (pintype "passive"))
      (node (ref "CC3") (pin "1") (pinfunction "1_1") (pintype "passive"))
      (node (ref "CC4") (pin "1") (pinfunction "1_1") (pintype "passive"))
      (node (ref "CC5") (pin "1") (pinfunction "1_1") (pintype "passive"))
      (node (ref "D2") (pin "1") (pinfunction "K_1") (pintype "bidirectional"))
      (node (ref "D4") (pin "2") (pinfunction "GND_2") (pintype "bidirectional"))
      (node (ref "EPD_C1") (pin "1") (pinfunction "1_1") (pintype "passive"))
      (node (ref "EPD_C10") (pin "1") (pinfunction "1_1") (pintype "passive"))
      (node (ref "EPD_C11") (pin "1") (pinfunction "1_1") (pintype "passive"))
      (node (ref "EPD_C12") (pin "1") (pinfunction "1_1") (pintype "passive"))
      (node (ref "EPD_C2") (pin "1") (pinfunction "1_1") (pintype "passive"))
      (node (ref "EPD_C5") (pin "1") (pinfunction "1_1") (pintype "passive"))
      (node (ref "EPD_C6") (pin "1") (pinfunction "1_1") (pintype "passive"))
      (node (ref "EPD_C7") (pin "1") (pinfunction "1_1") (pintype "passive"))
      (node (ref "EPD_C8") (pin "1") (pinfunction "1_1") (pintype "passive"))
      (node (ref "EPD_C9") (pin "1") (pinfunction "1_1") (pintype "passive"))
      (node (ref "IC1") (pin "D2") (pinfunction "GND_D2") (pintype "bidirectional"))
      (node (ref "IC2") (pin "B1") (pinfunction "VSEL_B1") (pintype "bidirectional"))
      (node (ref "IC2") (pin "C1") (pinfunction "AGND_C1") (pintype "bidirectional"))
      (node (ref "IC2") (pin "C2") (pinfunction "PGND_1_C2") (pintype "bidirectional"))
      (node (ref "IC2") (pin "C3") (pinfunction "PGND_2_C3") (pintype "bidirectional"))
      (node (ref "IC3") (pin "8") (pinfunction "GNDIO_8") (pintype "bidirectional"))
      (node (ref "IC3") (pin "9") (pinfunction "GND_9") (pintype "bidirectional"))
      (node (ref "IC4") (pin "B1") (pinfunction "IN/TRIG_B1") (pintype "bidirectional"))
      (node (ref "IC4") (pin "B3") (pinfunction "GND_B3") (pintype "bidirectional"))
      (node (ref "J1") (pin "3") (pinfunction "3_3") (pintype "bidirectional"))
      (node (ref "J1") (pin "5") (pinfunction "5_5") (pintype "bidirectional"))
      (node (ref "J2") (pin "17") (pinfunction "17_17") (pintype "bidirectional"))
      (node (ref "J2") (pin "8") (pinfunction "8_8") (pintype "bidirectional"))
      (node (ref "J2") (pin "MP1") (pinfunction "MP1_MP1") (pintype "bidirectional"))
      (node (ref "J2") (pin "MP2") (pinfunction "MP2_MP2") (pintype "bidirectional"))
      (node (ref "J3") (pin "A12_B1") (pinfunction "GND_A12_B1") (pintype "power_in"))
      (node (ref "J3") (pin "A1_B12") (pinfunction "GND_A1_B12") (pintype "power_in"))
      (node (ref "J3") (pin "SH1") (pinfunction "SHIELD_SH1") (pintype "passive"))
      (node (ref "J3") (pin "SH2") (pinfunction "SHIELD_SH2") (pintype "passive"))
      (node (ref "J3") (pin "SH3") (pinfunction "SHIELD_SH3") (pintype "passive"))
      (node (ref "J3") (pin "SH4") (pinfunction "SHIELD_SH4") (pintype "passive"))
      (node (ref "P1.01/2.4B") (pin "P$74") (pinfunction "VSS_PAD_P$74") (pintype "bidirectional"))
      (node (ref "P1.01/2.4B") (pin "P$75") (pinfunction "VSS_PAD_P$75") (pintype "bidirectional"))
      (node (ref "P1.01/2.4B") (pin "P$76") (pinfunction "VSS_PAD_P$76") (pintype "bidirectional"))
      (node (ref "P1.01/2.4B") (pin "P$77") (pinfunction "VSS_PAD_P$77") (pintype "bidirectional"))
      (node (ref "P1.01/2.4B") (pin "P$78") (pinfunction "VSS_PAD_P$78") (pintype "bidirectional"))
      (node (ref "P1.01/2.4B") (pin "P$79") (pinfunction "VSS_PAD_P$79") (pintype "bidirectional"))
      (node (ref "P1.01/2.4B") (pin "P$80") (pinfunction "VSS_PAD_P$80") (pintype "bidirectional"))
      (node (ref "P1.01/2.4B") (pin "P$81") (pinfunction "VSS_PAD_P$81") (pintype "bidirectional"))
      (node (ref "P1.01/2.4B") (pin "P$82") (pinfunction "VSS_PAD_P$82") (pintype "bidirectional"))
      (node (ref "P1.01/2.4B") (pin "P$83") (pinfunction "VSS_PAD_P$83") (pintype "bidirectional"))
      (node (ref "P1.01/2.4B") (pin "P$84") (pinfunction "VSS_PAD_P$84") (pintype "bidirectional"))
      (node (ref "P1.01/2.4B") (pin "P$85") (pinfunction "VSS_PAD_P$85") (pintype "bidirectional"))
      (node (ref "P1.01/2.4B") (pin "P$86") (pinfunction "VSS_PAD_P$86") (pintype "bidirectional"))
      (node (ref "P1.01/2.4B") (pin "P$87") (pinfunction "VSS_PAD_P$87") (pintype "bidirectional"))
      (node (ref "P1.01/2.4B") (pin "P$88") (pinfunction "VSS_PAD_P$88") (pintype "bidirectional"))
      (node (ref "P1.01/2.4B") (pin "P$89") (pinfunction "VSS_PAD_P$89") (pintype "bidirectional"))
      (node (ref "P1.01/2.4B") (pin "P$90") (pinfunction "VSS_PAD_P$90") (pintype "bidirectional"))
      (node (ref "P1.01/2.4B") (pin "P$B7") (pinfunction "VSS_P$B7") (pintype "power_in"))
      (node (ref "P1.01/2.4B") (pin "P$F23") (pinfunction "VSS_PA_P$F23") (pintype "bidirectional"))
      (node (ref "R14") (pin "2") (pinfunction "2_2") (pintype "bidirectional"))
      (node (ref "R15") (pin "1") (pinfunction "1_1") (pintype "bidirectional"))
      (node (ref "R2_EP_DR") (pin "1") (pinfunction "1_1") (pintype "bidirectional"))
      (node (ref "R8") (pin "2") (pinfunction "2_2") (pintype "bidirectional"))
      (node (ref "R9") (pin "1") (pinfunction "1_1") (pintype "bidirectional"))
      (node (ref "R_TYPE_SEL") (pin "1") (pinfunction "1_1") (pintype "bidirectional"))
      (node (ref "SJ1") (pin "1") (pinfunction "1_1") (pintype "passive"))
      (node (ref "SW1") (pin "1") (pinfunction "1_1") (pintype "passive"))
      (node (ref "SW2") (pin "1") (pinfunction "1_1") (pintype "passive"))
      (node (ref "SW3") (pin "1") (pinfunction "1_1") (pintype "passive"))
      (node (ref "TP_BAT_GND") (pin "TP") (pinfunction "TP_TP") (pintype "input"))
      (node (ref "TP_GND") (pin "TP") (pinfunction "TP_TP") (pintype "input"))
      (node (ref "U1") (pin "1") (pinfunction "CTG_1") (pintype "power_in"))
      (node (ref "U1") (pin "4") (pinfunction "GND_4") (pintype "power_in"))
      (node (ref "U1") (pin "6") (pinfunction "QSTRT_6") (pintype "input"))
      (node (ref "U1") (pin "9") (pinfunction "EP_9") (pintype "power_in"))
      (node (ref "X1") (pin "2") (pinfunction "2_2") (pintype "passive"))
      (node (ref "X1") (pin "4") (pinfunction "4_4") (pintype "passive"))
    )
    (net (code "14") (name "HAPTIC_EN") (class "Default")
      (node (ref "IC4") (pin "A1") (pinfunction "EN_A1") (pintype "bidirectional"))
      (node (ref "P1.01/2.4B") (pin "P$U1") (pinfunction "P0.12_P$U1") (pintype "bidirectional"))
    )
    (net (code "15") (name "IMU_INT1") (class "Default")
      (node (ref "IC3") (pin "5") (pinfunction "INT1_5") (pintype "bidirectional"))
      (node (ref "P1.01/2.4B") (pin "P$N1") (pinfunction "P0.08_P$N1") (pintype "bidirectional"))
    )
    (net (code "16") (name "IMU_INT2") (class "Default")
      (node (ref "IC3") (pin "6") (pinfunction "INT2_6") (pintype "bidirectional"))
      (node (ref "P1.01/2.4B") (pin "P$P2") (pinfunction "P1.08_P$P2") (pintype "bidirectional"))
    )
    (net (code "17") (name "LX1") (class "Default")
      (node (ref "IC2") (pin "B2") (pinfunction "SW1_1_B2") (pintype "bidirectional"))
      (node (ref "IC2") (pin "B3") (pinfunction "SW1_2_B3") (pintype "bidirectional"))
      (node (ref "L1") (pin "1") (pinfunction "1_1") (pintype "bidirectional"))
    )
    (net (code "18") (name "LX2") (class "Default")
      (node (ref "IC2") (pin "D2") (pinfunction "SW2_1_D2") (pintype "bidirectional"))
      (node (ref "IC2") (pin "D3") (pinfunction "SW2_2_D3") (pintype "bidirectional"))
      (node (ref "L1") (pin "2") (pinfunction "2_2") (pintype "bidirectional"))
    )
    (net (code "19") (name "MOSI") (class "Default")
      (node (ref "J2") (pin "14") (pinfunction "14_14") (pintype "bidirectional"))
      (node (ref "P1.01/2.4B") (pin "P$B13") (pinfunction "P0.03/AIN1_P$B13") (pintype "bidirectional"))
    )
    (net (code "20") (name "Net-(ANT1-FEED)") (class "Default")
      (node (ref "ANT1") (pin "1") (pinfunction "FEED_1") (pintype "input"))
      (node (ref "C22") (pin "2") (pinfunction "2_2") (pintype "passive"))
      (node (ref "CC4") (pin "2") (pinfunction "2_2") (pintype "passive"))
      (node (ref "LL1") (pin "2") (pinfunction "2_2") (pintype "passive"))
    )
    (net (code "21") (name "Net-(C5-Pad2)") (class "Default")
      (node (ref "C5") (pin "2") (pinfunction "2_2") (pintype "passive"))
      (node (ref "R11") (pin "1") (pinfunction "1_1") (pintype "bidirectional"))
    )
    (net (code "22") (name "Net-(C10-Pad2)") (class "Default")
      (node (ref "C10") (pin "2") (pinfunction "2_2") (pintype "passive"))
      (node (ref "R12") (pin "1") (pinfunction "1_1") (pintype "bidirectional"))
    )
    (net (code "23") (name "Net-(C11-Pad2)") (class "Default")
      (node (ref "C11") (pin "2") (pinfunction "2_2") (pintype "passive"))
      (node (ref "R13") (pin "1") (pinfunction "1_1") (pintype "bidirectional"))
    )
    (net (code "24") (name "Net-(C12-Pad1)") (class "Default")
      (node (ref "C12") (pin "1") (pinfunction "1_1") (pintype "passive"))
      (node (ref "P1.01/2.4B") (pin "P$A22") (pinfunction "VDD_P$A22") (pintype "power_in"))
    )
    (net (code "25") (name "Net-(D1-K)") (class "Default")
      (node (ref "C2-EP-DR") (pin "1") (pinfunction "1_1") (pintype "passive"))
      (node (ref "D1") (pin "1") (pinfunction "K_1") (pintype "bidirectional"))
      (node (ref "D2") (pin "2") (pinfunction "A_2") (pintype "bidirectional"))
    )
    (net (code "26") (name "Net-(D3-A)") (class "Default")
      (node (ref "C2-EP-DR") (pin "2") (pinfunction "2_2") (pintype "passive"))
      (node (ref "D3") (pin "2") (pinfunction "A_2") (pintype "bidirectional"))
      (node (ref "L5") (pin "1") (pinfunction "1_1") (pintype "passive"))
      (node (ref "Q2") (pin "3") (pinfunction "D_3") (pintype "bidirectional"))
    )
    (net (code "27") (name "Net-(EPD_C1-Pad2)") (class "Default")
      (node (ref "EPD_C1") (pin "2") (pinfunction "2_2") (pintype "passive"))
      (node (ref "J2") (pin "5") (pinfunction "5_5") (pintype "bidirectional"))
    )
    (net (code "28") (name "Net-(EPD_C2-Pad2)") (class "Default")
      (node (ref "EPD_C2") (pin "2") (pinfunction "2_2") (pintype "passive"))
      (node (ref "J2") (pin "4") (pinfunction "4_4") (pintype "bidirectional"))
    )
    (net (code "29") (name "Net-(EPD_C6-Pad2)") (class "Default")
      (node (ref "EPD_C6") (pin "2") (pinfunction "2_2") (pintype "passive"))
      (node (ref "J2") (pin "18") (pinfunction "18_18") (pintype "bidirectional"))
    )
    (net (code "30") (name "Net-(EPD_C7-Pad2)") (class "Default")
      (node (ref "EPD_C7") (pin "2") (pinfunction "2_2") (pintype "passive"))
      (node (ref "J2") (pin "19") (pinfunction "19_19") (pintype "bidirectional"))
    )
    (net (code "31") (name "Net-(EPD_C8-Pad2)") (class "Default")
      (node (ref "EPD_C8") (pin "2") (pinfunction "2_2") (pintype "passive"))
      (node (ref "J2") (pin "20") (pinfunction "20_20") (pintype "bidirectional"))
    )
    (net (code "32") (name "Net-(EPD_C10-Pad2)") (class "Default")
      (node (ref "EPD_C10") (pin "2") (pinfunction "2_2") (pintype "passive"))
      (node (ref "J2") (pin "22") (pinfunction "22_22") (pintype "bidirectional"))
    )
    (net (code "33") (name "Net-(EPD_C12-Pad2)") (class "Default")
      (node (ref "EPD_C12") (pin "2") (pinfunction "2_2") (pintype "passive"))
      (node (ref "J2") (pin "24") (pinfunction "24_24") (pintype "bidirectional"))
    )
    (net (code "34") (name "Net-(IC1-TS{slash}MR)") (class "Default")
      (node (ref "IC1") (pin "D1") (pinfunction "TS/MR_D1") (pintype "bidirectional"))
      (node (ref "R9") (pin "2") (pinfunction "2_2") (pintype "bidirectional"))
    )
    (net (code "35") (name "Net-(IC2-SCL)") (class "Default")
      (node (ref "IC2") (pin "D1") (pinfunction "SCL_D1") (pintype "bidirectional"))
      (node (ref "R2") (pin "2") (pinfunction "2_2") (pintype "bidirectional"))
    )
    (net (code "36") (name "Net-(IC2-SDA)") (class "Default")
      (node (ref "IC2") (pin "E1") (pinfunction "SDA_E1") (pintype "bidirectional"))
      (node (ref "R3") (pin "2") (pinfunction "2_2") (pintype "bidirectional"))
    )
    (net (code "37") (name "Net-(IC3-SDO)") (class "Default")
      (node (ref "IC3") (pin "1") (pinfunction "SDO_1") (pintype "bidirectional"))
      (node (ref "R8") (pin "1") (pinfunction "1_1") (pintype "bidirectional"))
    )
    (net (code "38") (name "Net-(IC4-REG)") (class "Default")
      (node (ref "C3") (pin "2") (pinfunction "2_2") (pintype "passive"))
      (node (ref "IC4") (pin "A2") (pinfunction "REG_A2") (pintype "bidirectional"))
    )
    (net (code "39") (name "Net-(J3-CC1)") (class "Default")
      (node (ref "J3") (pin "A5") (pinfunction "CC1_A5") (pintype "bidirectional"))
      (node (ref "R14") (pin "1") (pinfunction "1_1") (pintype "bidirectional"))
    )
    (net (code "40") (name "Net-(J3-CC2)") (class "Default")
      (node (ref "J3") (pin "B5") (pinfunction "CC2_B5") (pintype "bidirectional"))
      (node (ref "R15") (pin "2") (pinfunction "2_2") (pintype "bidirectional"))
    )
    (net (code "41") (name "Net-(LL2-Pad1)") (class "Default")
      (node (ref "LL2") (pin "1") (pinfunction "1_1") (pintype "passive"))
      (node (ref "LL3") (pin "2") (pinfunction "2_2") (pintype "passive"))
    )
    (net (code "42") (name "Net-(P1.01/2.4B-ANT)") (class "Default")
      (node (ref "CC3") (pin "2") (pinfunction "2_2") (pintype "passive"))
      (node (ref "LL1") (pin "1") (pinfunction "1_1") (pintype "passive"))
      (node (ref "P1.01/2.4B") (pin "P$H23") (pinfunction "ANT_P$H23") (pintype "bidirectional"))
    )
    (net (code "43") (name "Net-(P1.01/2.4B-DCC)") (class "Default")
      (node (ref "LL2") (pin "2") (pinfunction "2_2") (pintype "passive"))
      (node (ref "P1.01/2.4B") (pin "P$B3") (pinfunction "DCC_P$B3") (pintype "output"))
    )
    (net (code "44") (name "Net-(P1.01/2.4B-DEC1)") (class "Default")
      (node (ref "CC5") (pin "2") (pinfunction "2_2") (pintype "passive"))
      (node (ref "P1.01/2.4B") (pin "P$C1") (pinfunction "DEC1_P$C1") (pintype "power_in"))
    )
    (net (code "45") (name "Net-(P1.01/2.4B-DEC2)") (class "Default")
      (node (ref "C13") (pin "1") (pinfunction "1_1") (pintype "passive"))
      (node (ref "P1.01/2.4B") (pin "P$A18") (pinfunction "DEC2_P$A18") (pintype "bidirectional"))
    )
    (net (code "46") (name "Net-(P1.01/2.4B-DEC3)") (class "Default")
      (node (ref "CC11") (pin "1") (pinfunction "1_1") (pintype "passive"))
      (node (ref "P1.01/2.4B") (pin "P$D23") (pinfunction "DEC3_P$D23") (pintype "bidirectional"))
    )
    (net (code "47") (name "Net-(P1.01/2.4B-DEC3V3)") (class "Default")
      (node (ref "C20") (pin "2") (pinfunction "2_2") (pintype "passive"))
      (node (ref "P1.01/2.4B") (pin "P$AC5") (pinfunction "DEC3V3_P$AC5") (pintype "bidirectional"))
    )
    (net (code "48") (name "Net-(P1.01/2.4B-DEC4)") (class "Default")
      (node (ref "C15") (pin "1") (pinfunction "1_1") (pintype "passive"))
      (node (ref "C16") (pin "1") (pinfunction "1_1") (pintype "passive"))
      (node (ref "CC10") (pin "1") (pinfunction "1_1") (pintype "passive"))
      (node (ref "LL3") (pin "1") (pinfunction "1_1") (pintype "passive"))
      (node (ref "P1.01/2.4B") (pin "P$B5") (pinfunction "DEC4_P$B5") (pintype "power_in"))
      (node (ref "P1.01/2.4B") (pin "P$E24") (pinfunction "DEC6_P$E24") (pintype "bidirectional"))
    )
    (net (code "49") (name "Net-(P1.01/2.4B-DEC5)") (class "Default")
      (node (ref "C9") (pin "1") (pinfunction "1_1") (pintype "passive"))
      (node (ref "P1.01/2.4B") (pin "P$N24") (pinfunction "DEC5_P$N24") (pintype "bidirectional"))
    )
    (net (code "50") (name "Net-(P1.01/2.4B-P0.00{slash}XL1)") (class "Default")
      (node (ref "C17") (pin "1") (pinfunction "1_1") (pintype "passive"))
      (node (ref "P1.01/2.4B") (pin "P$D2") (pinfunction "P0.00/XL1_P$D2") (pintype "bidirectional"))
      (node (ref "X2") (pin "2") (pinfunction "2_2") (pintype "passive"))
    )
    (net (code "51") (name "Net-(P1.01/2.4B-P0.01{slash}XL2)") (class "Default")
      (node (ref "C18") (pin "1") (pinfunction "1_1") (pintype "passive"))
      (node (ref "P1.01/2.4B") (pin "P$F2") (pinfunction "P0.01/XL2_P$F2") (pintype "bidirectional"))
      (node (ref "X2") (pin "1") (pinfunction "1_1") (pintype "passive"))
    )
    (net (code "52") (name "Net-(P1.01/2.4B-XC1)") (class "Default")
      (node (ref "CC1") (pin "1") (pinfunction "1_1") (pintype "passive"))
      (node (ref "P1.01/2.4B") (pin "P$B24") (pinfunction "XC1_P$B24") (pintype "input"))
      (node (ref "X1") (pin "1") (pinfunction "1_1") (pintype "passive"))
    )
    (net (code "53") (name "Net-(P1.01/2.4B-XC2)") (class "Default")
      (node (ref "CC2") (pin "1") (pinfunction "1_1") (pintype "passive"))
      (node (ref "P1.01/2.4B") (pin "P$A23") (pinfunction "XC2_P$A23") (pintype "output"))
      (node (ref "X1") (pin "3") (pinfunction "3_3") (pintype "passive"))
    )
    (net (code "54") (name "Net-(Q2-S)") (class "Default")
      (node (ref "Q2") (pin "2") (pinfunction "S_2") (pintype "bidirectional"))
      (node (ref "R1_EP_DR") (pin "2") (pinfunction "2_2") (pintype "bidirectional"))
    )
    (net (code "55") (name "Net-(R1_EP_DR-Pad1)") (class "Default")
      (node (ref "R1_EP_DR") (pin "1") (pinfunction "1_1") (pintype "bidirectional"))
      (node (ref "R_TYPE_SEL") (pin "2") (pinfunction "2_2") (pintype "bidirectional"))
      (node (ref "SJ1") (pin "2") (pinfunction "2_2") (pintype "passive"))
    )
    (net (code "56") (name "OUT+") (class "Default")
      (node (ref "IC4") (pin "A3") (pinfunction "OUT+_A3") (pintype "bidirectional"))
      (node (ref "TP_OP") (pin "TP") (pinfunction "TP_TP") (pintype "input"))
    )
    (net (code "57") (name "OUT-") (class "Default")
      (node (ref "IC4") (pin "C3") (pinfunction "OUT-_C3") (pintype "bidirectional"))
      (node (ref "TP_ON") (pin "TP") (pinfunction "TP_TP") (pintype "input"))
    )
    (net (code "58") (name "P0.04") (class "Default")
      (node (ref "P1.01/2.4B") (pin "P$J1") (pinfunction "P0.04/AIN2_P$J1") (pintype "bidirectional"))
    )
    (net (code "59") (name "P0.09") (class "Default")
      (node (ref "P1.01/2.4B") (pin "P$L24") (pinfunction "P0.09/NFC1_P$L24") (pintype "bidirectional"))
    )
    (net (code "60") (name "P0.13") (class "Default")
      (node (ref "P1.01/2.4B") (pin "P$AD8") (pinfunction "P0.13_P$AD8") (pintype "bidirectional"))
      (node (ref "SW1") (pin "2") (pinfunction "2_2") (pintype "passive"))
    )
    (net (code "61") (name "P0.14") (class "Default")
      (node (ref "P1.01/2.4B") (pin "P$AC9") (pinfunction "P0.14_P$AC9") (pintype "bidirectional"))
      (node (ref "SW2") (pin "2") (pinfunction "2_2") (pintype "passive"))
    )
    (net (code "62") (name "P0.19") (class "Default")
      (node (ref "P1.01/2.4B") (pin "P$AC15") (pinfunction "P0.19_P$AC15") (pintype "bidirectional"))
    )
    (net (code "63") (name "P0.20") (class "Default")
      (node (ref "P1.01/2.4B") (pin "P$AD16") (pinfunction "P0.20_P$AD16") (pintype "bidirectional"))
    )
    (net (code "64") (name "P0.21") (class "Default")
      (node (ref "P1.01/2.4B") (pin "P$AC17") (pinfunction "P0.21_P$AC17") (pintype "bidirectional"))
    )
    (net (code "65") (name "P0.22") (class "Default")
      (node (ref "P1.01/2.4B") (pin "P$AD18") (pinfunction "P0.22_P$AD18") (pintype "bidirectional"))
    )
    (net (code "66") (name "P0.23") (class "Default")
      (node (ref "P1.01/2.4B") (pin "P$AC19") (pinfunction "P0.23_P$AC19") (pintype "bidirectional"))
    )
    (net (code "67") (name "P0.24") (class "Default")
      (node (ref "P1.01/2.4B") (pin "P$AD20") (pinfunction "P0.24_P$AD20") (pintype "bidirectional"))
    )
    (net (code "68") (name "P0.25") (class "Default")
      (node (ref "P1.01/2.4B") (pin "P$AC21") (pinfunction "P0.25_P$AC21") (pintype "bidirectional"))
    )
    (net (code "69") (name "P0.26") (class "Default")
      (node (ref "P1.01/2.4B") (pin "P$G1") (pinfunction "P0.26_P$G1") (pintype "bidirectional"))
    )
    (net (code "70") (name "P0.27") (class "Default")
      (node (ref "P1.01/2.4B") (pin "P$H2") (pinfunction "P0.27_P$H2") (pintype "bidirectional"))
    )
    (net (code "71") (name "P0.28") (class "Default")
      (node (ref "P1.01/2.4B") (pin "P$B11") (pinfunction "P0.28/AIN4_P$B11") (pintype "bidirectional"))
    )
    (net (code "72") (name "P0.29") (class "Default")
      (node (ref "P1.01/2.4B") (pin "P$A10") (pinfunction "P0.29/AIN5_P$A10") (pintype "bidirectional"))
    )
    (net (code "73") (name "P0.30") (class "Default")
      (node (ref "P1.01/2.4B") (pin "P$B9") (pinfunction "P0.30/AIN6_P$B9") (pintype "bidirectional"))
    )
    (net (code "74") (name "P0.31") (class "Default")
      (node (ref "P1.01/2.4B") (pin "P$A8") (pinfunction "P0.31/AIN7_P$A8") (pintype "bidirectional"))
    )
    (net (code "75") (name "P1.01") (class "Default")
      (node (ref "DMG2305UX-7") (pin "1") (pinfunction "G_1") (pintype "bidirectional"))
      (node (ref "P1.01/2.4B") (pin "P$Y23") (pinfunction "P1.01_P$Y23") (pintype "bidirectional"))
      (node (ref "R_PWR_EPD") (pin "1") (pinfunction "1_1") (pintype "bidirectional"))
    )
    (net (code "76") (name "P1.02") (class "Default")
      (node (ref "P1.01/2.4B") (pin "P$W24") (pinfunction "P1.02_P$W24") (pintype "bidirectional"))
      (node (ref "SW3") (pin "2") (pinfunction "2_2") (pintype "passive"))
    )
    (net (code "77") (name "P1.03") (class "Default")
      (node (ref "P1.01/2.4B") (pin "P$V23") (pinfunction "P1.03_P$V23") (pintype "bidirectional"))
    )
    (net (code "78") (name "P1.04") (class "Default")
      (node (ref "P1.01/2.4B") (pin "P$U24") (pinfunction "P1.04_P$U24") (pintype "bidirectional"))
    )
    (net (code "79") (name "P1.05") (class "Default")
      (node (ref "P1.01/2.4B") (pin "P$T23") (pinfunction "P1.05_P$T23") (pintype "bidirectional"))
    )
    (net (code "80") (name "P1.06") (class "Default")
      (node (ref "P1.01/2.4B") (pin "P$R24") (pinfunction "P1.06_P$R24") (pintype "bidirectional"))
    )
    (net (code "81") (name "P1.07") (class "Default")
      (node (ref "P1.01/2.4B") (pin "P$P23") (pinfunction "P1.07_P$P23") (pintype "bidirectional"))
    )
    (net (code "82") (name "P1.09") (class "Default")
      (node (ref "P1.01/2.4B") (pin "P$R1") (pinfunction "P1.09_P$R1") (pintype "bidirectional"))
    )
    (net (code "83") (name "P1.10") (class "Default")
      (node (ref "P1.01/2.4B") (pin "P$A20") (pinfunction "P1.10_P$A20") (pintype "bidirectional"))
    )
    (net (code "84") (name "P1.11") (class "Default")
      (node (ref "P1.01/2.4B") (pin "P$B19") (pinfunction "P1.11_P$B19") (pintype "bidirectional"))
    )
    (net (code "85") (name "P1.12") (class "Default")
      (node (ref "P1.01/2.4B") (pin "P$B17") (pinfunction "P1.12_P$B17") (pintype "bidirectional"))
    )
    (net (code "86") (name "P1.13") (class "Default")
      (node (ref "P1.01/2.4B") (pin "P$A16") (pinfunction "P1.13_P$A16") (pintype "bidirectional"))
    )
    (net (code "87") (name "P1.14") (class "Default")
      (node (ref "P1.01/2.4B") (pin "P$B15") (pinfunction "P1.14_P$B15") (pintype "bidirectional"))
    )
    (net (code "88") (name "P1.15") (class "Default")
      (node (ref "P1.01/2.4B") (pin "P$A14") (pinfunction "P1.15_P$A14") (pintype "bidirectional"))
    )
    (net (code "89") (name "PMIC_INT") (class "Default")
      (node (ref "IC1") (pin "A1") (pinfunction "~{INT}_A1") (pintype "bidirectional"))
      (node (ref "P1.01/2.4B") (pin "P$T2") (pinfunction "P0.11_P$T2") (pintype "bidirectional"))
    )
    (net (code "90") (name "PREVGH") (class "Default")
      (node (ref "D3") (pin "1") (pinfunction "K_1") (pintype "bidirectional"))
      (node (ref "EPD_C9") (pin "2") (pinfunction "2_2") (pintype "passive"))
      (node (ref "J2") (pin "21") (pinfunction "21_21") (pintype "bidirectional"))
    )
    (net (code "91") (name "PREVGL") (class "Default")
      (node (ref "D1") (pin "2") (pinfunction "A_2") (pintype "bidirectional"))
      (node (ref "EPD_C11") (pin "2") (pinfunction "2_2") (pintype "passive"))
      (node (ref "J2") (pin "23") (pinfunction "23_23") (pintype "bidirectional"))
    )
    (net (code "92") (name "RESE") (class "Default")
      (node (ref "J2") (pin "3") (pinfunction "3_3") (pintype "bidirectional"))
    )
    (net (code "93") (name "RESET") (class "Default")
      (node (ref "J1") (pin "6") (pinfunction "6_6") (pintype "bidirectional"))
      (node (ref "P1.01/2.4B") (pin "P$AC13") (pinfunction "P0.18/RESET_P$AC13") (pintype "bidirectional"))
      (node (ref "TP_RESET") (pin "TP") (pinfunction "TP_TP") (pintype "input"))
    )
    (net (code "94") (name "SCK") (class "Default")
      (node (ref "J2") (pin "13") (pinfunction "13_13") (pintype "bidirectional"))
      (node (ref "P1.01/2.4B") (pin "P$A12") (pinfunction "P0.02/AIN0_P$A12") (pintype "bidirectional"))
    )
    (net (code "95") (name "SCL") (class "Default")
      (node (ref "IC1") (pin "B1") (pinfunction "SCL_B1") (pintype "bidirectional"))
      (node (ref "IC3") (pin "12") (pinfunction "SCX_12") (pintype "bidirectional"))
      (node (ref "IC4") (pin "C1") (pinfunction "SCL_C1") (pintype "bidirectional"))
      (node (ref "P1.01/2.4B") (pin "P$M2") (pinfunction "P0.07_P$M2") (pintype "bidirectional"))
      (node (ref "R2") (pin "1") (pinfunction "1_1") (pintype "bidirectional"))
      (node (ref "R4") (pin "1") (pinfunction "1_1") (pintype "bidirectional"))
      (node (ref "TP_SCL") (pin "TP") (pinfunction "TP_TP") (pintype "input"))
      (node (ref "U1") (pin "7") (pinfunction "SCL_7") (pintype "input"))
    )
    (net (code "96") (name "SDA") (class "Default")
      (node (ref "IC1") (pin "C1") (pinfunction "SDA_C1") (pintype "bidirectional"))
      (node (ref "IC3") (pin "2") (pinfunction "SDX_2") (pintype "bidirectional"))
      (node (ref "IC4") (pin "B2") (pinfunction "SDA_B2") (pintype "bidirectional"))
      (node (ref "P1.01/2.4B") (pin "P$L1") (pinfunction "P0.06_P$L1") (pintype "bidirectional"))
      (node (ref "R3") (pin "1") (pinfunction "1_1") (pintype "bidirectional"))
      (node (ref "R5") (pin "1") (pinfunction "1_1") (pintype "bidirectional"))
      (node (ref "TP_SDA") (pin "TP") (pinfunction "TP_TP") (pintype "input"))
      (node (ref "U1") (pin "8") (pinfunction "SDA_8") (pintype "bidirectional"))
    )
    (net (code "97") (name "SWDCLK") (class "Default")
      (node (ref "J1") (pin "4") (pinfunction "4_4") (pintype "bidirectional"))
      (node (ref "P1.01/2.4B") (pin "P$AA24") (pinfunction "SWDCLK_P$AA24") (pintype "input"))
      (node (ref "TP_SWDCLK") (pin "TP") (pinfunction "TP_TP") (pintype "input"))
    )
    (net (code "98") (name "SWDIO") (class "Default")
      (node (ref "J1") (pin "2") (pinfunction "2_2") (pintype "bidirectional"))
      (node (ref "P1.01/2.4B") (pin "P$AC24") (pinfunction "SWDIO_P$AC24") (pintype "bidirectional"))
      (node (ref "TP_SWDIO") (pin "TP") (pinfunction "TP_TP") (pintype "input"))
    )
    (net (code "99") (name "SWO") (class "Default")
      (node (ref "P1.01/2.4B") (pin "P$AD22") (pinfunction "P1.00_P$AD22") (pintype "bidirectional"))
      (node (ref "TP_SWO") (pin "TP") (pinfunction "TP_TP") (pintype "input"))
    )
    (net (code "100") (name "VBAT") (class "Default")
      (node (ref "C2") (pin "2") (pinfunction "2_2") (pintype "passive"))
      (node (ref "C37") (pin "1") (pinfunction "1_1") (pintype "passive"))
      (node (ref "IC1") (pin "C2") (pinfunction "BAT_C2") (pintype "bidirectional"))
      (node (ref "TP_VBAT") (pin "TP") (pinfunction "TP_TP") (pintype "input"))
      (node (ref "U1") (pin "2") (pinfunction "CELL_2") (pintype "power_in"))
      (node (ref "U1") (pin "3") (pinfunction "VDD_3") (pintype "power_in"))
    )
    (net (code "101") (name "VBUS") (class "Default")
      (node (ref "C21") (pin "1") (pinfunction "1_1") (pintype "passive"))
      (node (ref "C38") (pin "1") (pinfunction "1_1") (pintype "passive"))
      (node (ref "C42") (pin "2") (pinfunction "2_2") (pintype "passive"))
      (node (ref "C43") (pin "1") (pinfunction "1_1") (pintype "passive"))
      (node (ref "D4") (pin "5") (pinfunction "VBUS_5") (pintype "bidirectional"))
      (node (ref "IC1") (pin "A2") (pinfunction "IN_A2") (pintype "bidirectional"))
      (node (ref "J3") (pin "A4_B9") (pinfunction "VBUS_A4_B9") (pintype "power_in"))
      (node (ref "J3") (pin "A9_B4") (pinfunction "VBUS_A9_B4") (pintype "power_in"))
      (node (ref "P1.01/2.4B") (pin "P$AD2") (pinfunction "VBUS_P$AD2") (pintype "power_in"))
    )
    (net (code "102") (name "VREG") (class "Default")
      (node (ref "C23") (pin "2") (pinfunction "2_2") (pintype "passive"))
      (node (ref "C24") (pin "2") (pinfunction "2_2") (pintype "passive"))
      (node (ref "C39") (pin "1") (pinfunction "1_1") (pintype "passive"))
      (node (ref "IC1") (pin "B2") (pinfunction "SYS_B2") (pintype "bidirectional"))
      (node (ref "IC2") (pin "A1") (pinfunction "EN_A1") (pintype "bidirectional"))
      (node (ref "IC2") (pin "A2") (pinfunction "VIN_1_A2") (pintype "bidirectional"))
      (node (ref "IC2") (pin "A3") (pinfunction "VIN_2_A3") (pintype "bidirectional"))
      (node (ref "TP_VREG") (pin "TP") (pinfunction "TP_TP") (pintype "input"))
    )
    (net (code "103") (name "unconnected-(ANT1-NC-Pad2)") (class "Default")
      (node (ref "ANT1") (pin "2") (pinfunction "NC_2") (pintype "no_connect"))
    )
    (net (code "104") (name "unconnected-(IC3-ASCL-Pad11)") (class "Default")
      (node (ref "IC3") (pin "11") (pinfunction "ASCL_11") (pintype "bidirectional"))
    )
    (net (code "105") (name "unconnected-(IC3-ASDA-Pad4)") (class "Default")
      (node (ref "IC3") (pin "4") (pinfunction "ASDA_4") (pintype "bidirectional"))
    )
    (net (code "106") (name "unconnected-(J2-Pad1)") (class "Default")
      (node (ref "J2") (pin "1") (pinfunction "1_1") (pintype "bidirectional"))
    )
    (net (code "107") (name "unconnected-(J2-Pad6)") (class "Default")
      (node (ref "J2") (pin "6") (pinfunction "6_6") (pintype "bidirectional"))
    )
    (net (code "108") (name "unconnected-(J2-Pad7)") (class "Default")
      (node (ref "J2") (pin "7") (pinfunction "7_7") (pintype "bidirectional"))
    )
    (net (code "109") (name "unconnected-(J3-SBU1-PadA8)") (class "Default")
      (node (ref "J3") (pin "A8") (pinfunction "SBU1_A8") (pintype "bidirectional"))
    )
    (net (code "110") (name "unconnected-(J3-SBU2-PadB8)") (class "Default")
      (node (ref "J3") (pin "B8") (pinfunction "SBU2_B8") (pintype "bidirectional"))
    )
    (net (code "111") (name "unconnected-(P1.01/2.4B-DCCH-PadP$AB2)") (class "Default")
      (node (ref "P1.01/2.4B") (pin "P$AB2") (pinfunction "DCCH_P$AB2") (pintype "bidirectional"))
    )
  )
)
